# EtherIOv3_1.net
KiCad netlist of a schematic drawn in Altium Designer
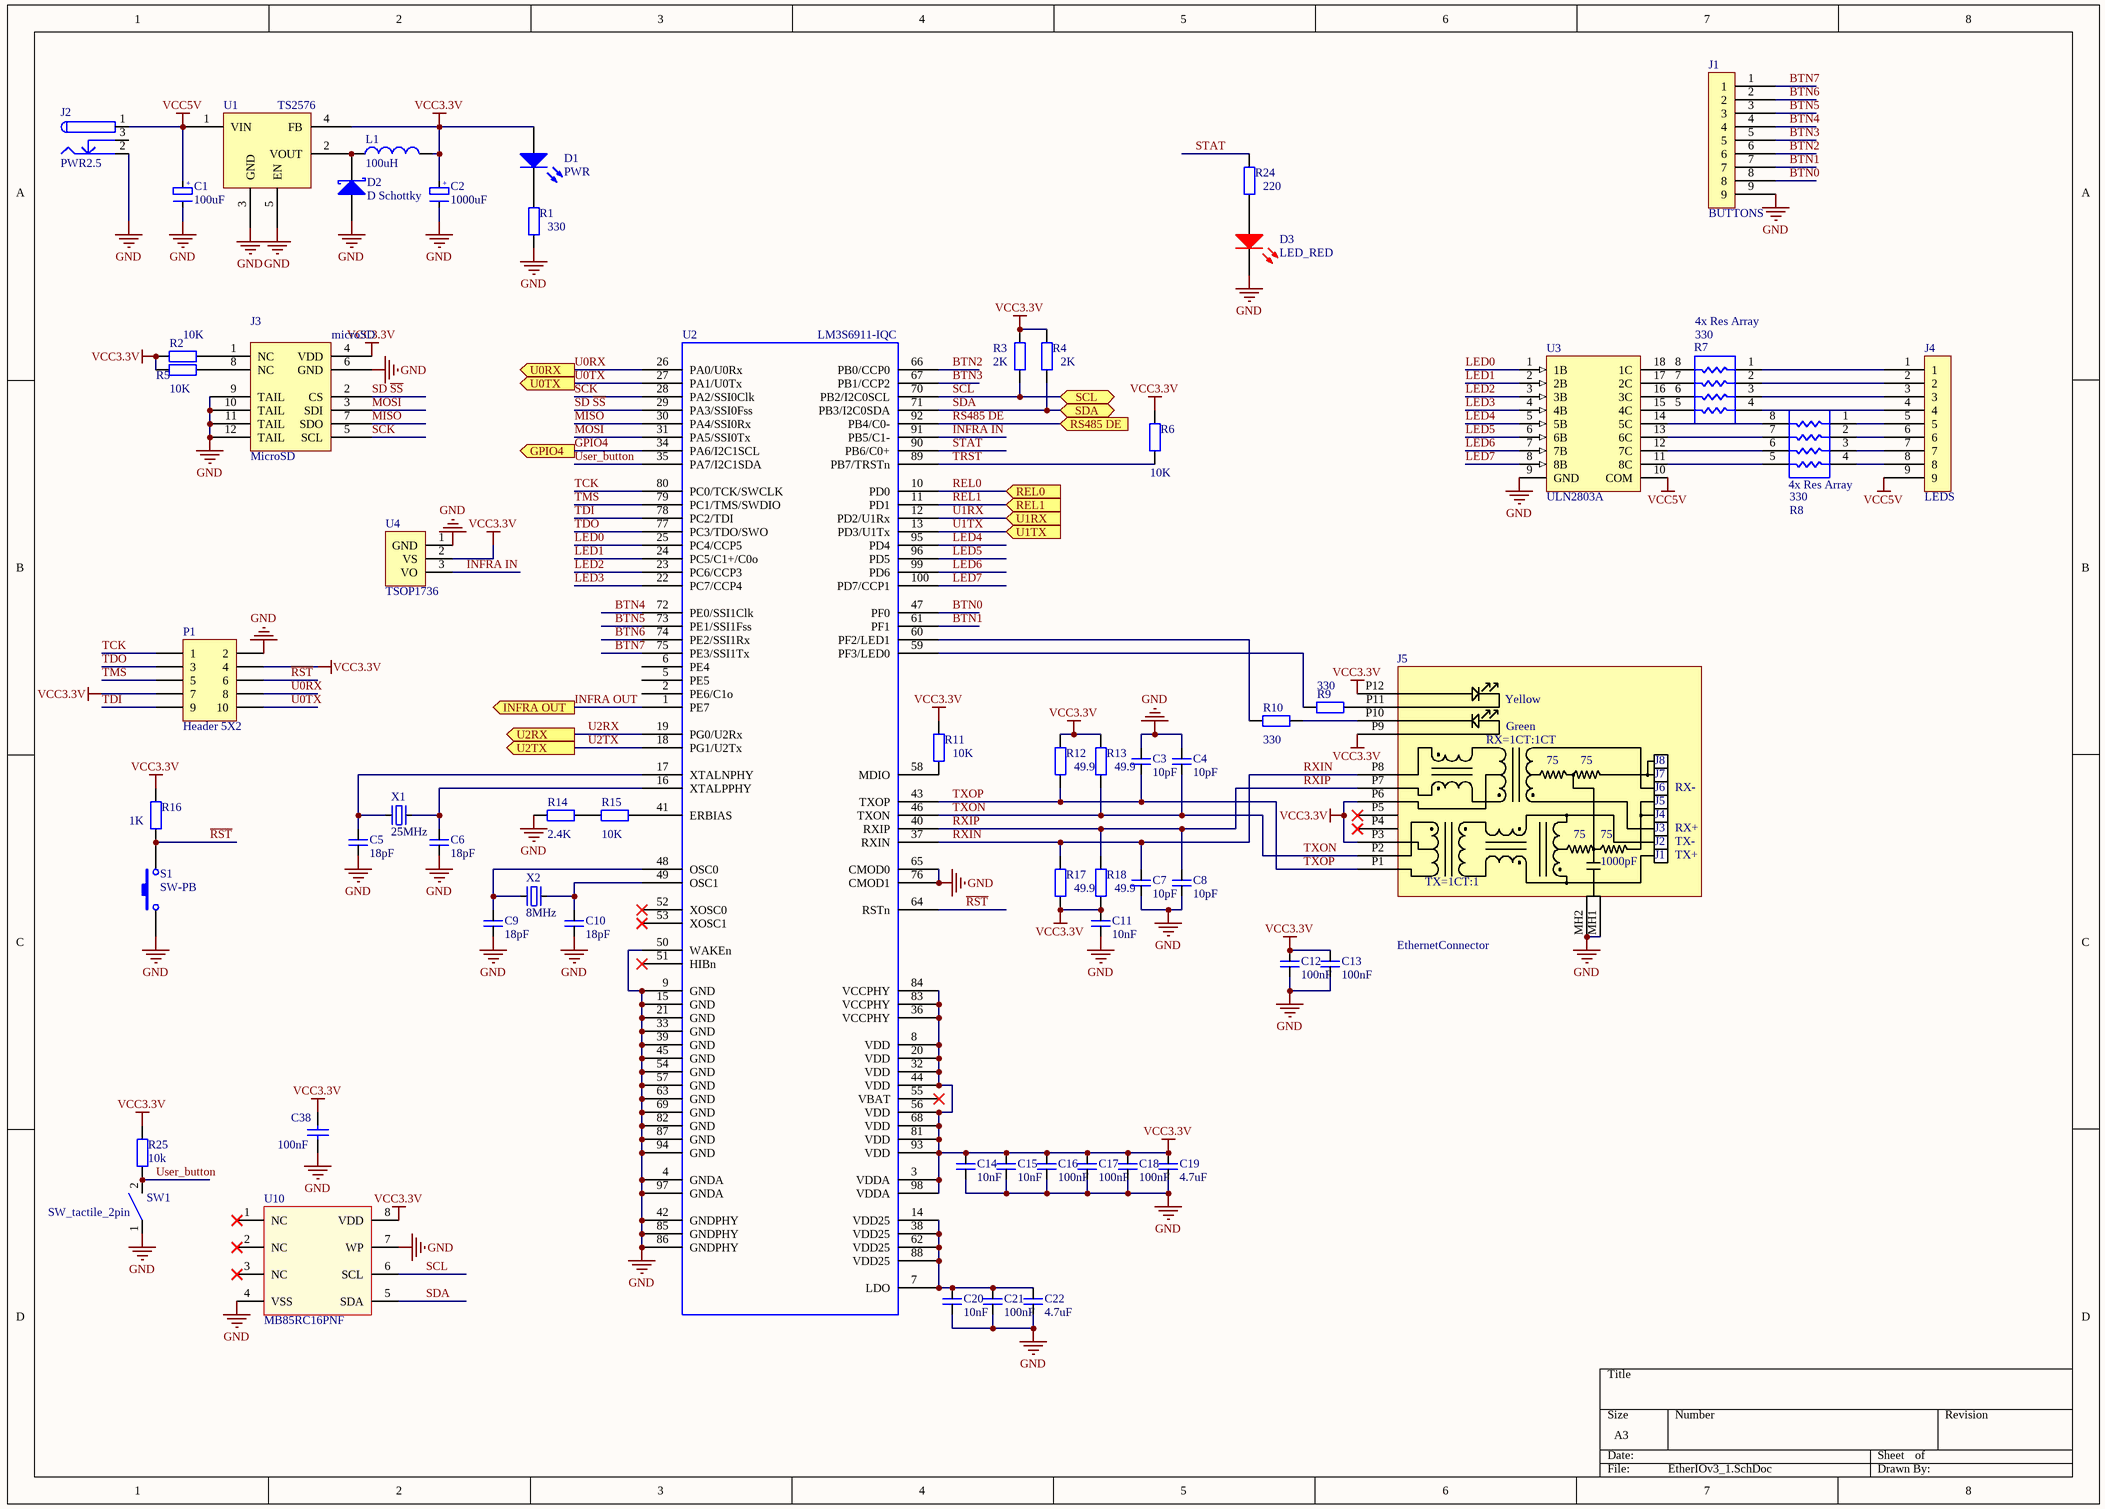
[diagram p0: EtherIOv3_1.SchDoc]

(export (version "E")
  (design (tool "Eeschema 10.0.6"))
  (components
    (comp (ref "C1")
      (value "100uF")
      (footprint "Electrolit Cap F80")
      (description "SMD Electrolit Capacitor")
      (fields (field (name "Comment") "100uF_25V"))
      (libsource (lib "EtherIOv2") (part "100uF_25V"))
    )
    (comp (ref "C2")
      (value "1000uF")
      (footprint "Electrolit Cap J10")
      (description "SMD Electrolit Capacitor")
      (fields (field (name "Comment") "1000uF_6V3"))
      (libsource (lib "EtherIOv2") (part "1000uF_6V3"))
    )
    (comp (ref "C3")
      (value "10pF")
      (footprint "0805 CAP")
      (description "Capacitor")
      (fields (field (name "Comment") "CAP"))
      (libsource (lib "EtherIOv2") (part "CAP"))
    )
    (comp (ref "C4")
      (value "10pF")
      (footprint "0805 CAP")
      (description "Capacitor")
      (fields (field (name "Comment") "CAP"))
      (libsource (lib "EtherIOv2") (part "CAP"))
    )
    (comp (ref "C5")
      (value "18pF")
      (footprint "0805 CAP")
      (description "Capacitor")
      (fields (field (name "Comment") "CAP"))
      (libsource (lib "EtherIOv2") (part "CAP"))
    )
    (comp (ref "C6")
      (value "18pF")
      (footprint "0805 CAP")
      (description "Capacitor")
      (fields (field (name "Comment") "CAP"))
      (libsource (lib "EtherIOv2") (part "CAP"))
    )
    (comp (ref "C7")
      (value "10pF")
      (footprint "0805 CAP")
      (description "Capacitor")
      (fields (field (name "Comment") "CAP"))
      (libsource (lib "EtherIOv2") (part "CAP"))
    )
    (comp (ref "C8")
      (value "10pF")
      (footprint "0805 CAP")
      (description "Capacitor")
      (fields (field (name "Comment") "CAP"))
      (libsource (lib "EtherIOv2") (part "CAP"))
    )
    (comp (ref "C9")
      (value "18pF")
      (footprint "0805 CAP")
      (description "Capacitor")
      (fields (field (name "Comment") "CAP"))
      (libsource (lib "EtherIOv2") (part "CAP"))
    )
    (comp (ref "C10")
      (value "18pF")
      (footprint "0805 CAP")
      (description "Capacitor")
      (fields (field (name "Comment") "CAP"))
      (libsource (lib "EtherIOv2") (part "CAP"))
    )
    (comp (ref "C11")
      (value "10nF")
      (footprint "0805 CAP")
      (description "Capacitor")
      (fields (field (name "Comment") "CAP"))
      (libsource (lib "EtherIOv2") (part "CAP"))
    )
    (comp (ref "C12")
      (value "100nF")
      (footprint "0805 CAP")
      (description "Capacitor")
      (fields (field (name "Comment") "CAP"))
      (libsource (lib "EtherIOv2") (part "CAP"))
    )
    (comp (ref "C13")
      (value "100nF")
      (footprint "0805 CAP")
      (description "Capacitor")
      (fields (field (name "Comment") "CAP"))
      (libsource (lib "EtherIOv2") (part "CAP"))
    )
    (comp (ref "C14")
      (value "10nF")
      (footprint "0805 CAP")
      (description "Capacitor")
      (fields (field (name "Comment") "CAP"))
      (libsource (lib "EtherIOv2") (part "CAP"))
    )
    (comp (ref "C15")
      (value "10nF")
      (footprint "0805 CAP")
      (description "Capacitor")
      (fields (field (name "Comment") "CAP"))
      (libsource (lib "EtherIOv2") (part "CAP"))
    )
    (comp (ref "C16")
      (value "100nF")
      (footprint "0805 CAP")
      (description "Capacitor")
      (fields (field (name "Comment") "CAP"))
      (libsource (lib "EtherIOv2") (part "CAP"))
    )
    (comp (ref "C17")
      (value "100nF")
      (footprint "0805 CAP")
      (description "Capacitor")
      (fields (field (name "Comment") "CAP"))
      (libsource (lib "EtherIOv2") (part "CAP"))
    )
    (comp (ref "C18")
      (value "100nF")
      (footprint "0805 CAP")
      (description "Capacitor")
      (fields (field (name "Comment") "CAP"))
      (libsource (lib "EtherIOv2") (part "CAP"))
    )
    (comp (ref "C19")
      (value "4.7uF")
      (footprint "0805 CAP")
      (description "Capacitor")
      (fields (field (name "Comment") "CAP"))
      (libsource (lib "EtherIOv2") (part "CAP"))
    )
    (comp (ref "C20")
      (value "10nF")
      (footprint "0805 CAP")
      (description "Capacitor")
      (fields (field (name "Comment") "CAP"))
      (libsource (lib "EtherIOv2") (part "CAP"))
    )
    (comp (ref "C21")
      (value "100nF")
      (footprint "0805 CAP")
      (description "Capacitor")
      (fields (field (name "Comment") "CAP"))
      (libsource (lib "EtherIOv2") (part "CAP"))
    )
    (comp (ref "C22")
      (value "4.7uF")
      (footprint "0805 CAP")
      (description "Capacitor")
      (fields (field (name "Comment") "CAP"))
      (libsource (lib "EtherIOv2") (part "CAP"))
    )
    (comp (ref "C38")
      (value "100nF")
      (footprint "FP_0805_CAP_125")
      (description "Capacitor")
      (libsource (lib "Miscellaneous Devices") (part "Cap"))
    )
    (comp (ref "D1")
      (value "PWR")
      (footprint "0805 LED")
      (description "Typical RED, GREEN, YELLOW, AMBER GaAs LED")
      (fields (field (name "PUBLISHER") "Altium Limited"))
      (libsource (lib "Miscellaneous Devices") (part "LED2"))
    )
    (comp (ref "D2")
      (value "D Schottky")
      (footprint "DSO-C2/X2.3")
      (description "Schottky Diode")
      (fields (field (name "PUBLISHER") "Altium Limited"))
      (libsource (lib "Miscellaneous Devices") (part "D Schottky"))
    )
    (comp (ref "D3")
      (value "LED_RED")
      (footprint "Osram sideled")
      (description "Typical LED")
      (libsource (lib "Led_optical") (part "LED_R"))
    )
    (comp (ref "J1")
      (value "BUTTONS")
      (footprint "Euroblock 3.5pitch 9P")
      (libsource (lib "") (part "Euroblock 9P connector_1"))
    )
    (comp (ref "J2")
      (value "PWR2.5")
      (footprint "KLD-0202")
      (description "Low Voltage Power Supply Connector")
      (fields (field (name "PUBLISHER") "Altium Limited"))
      (libsource (lib "EtherIOv2") (part "PWR2.5"))
    )
    (comp (ref "J3") (value "MicroSD") (footprint "microSD") (libsource (lib "Waterstars") (part "MicroSD")))
    (comp (ref "J4")
      (value "LEDS")
      (footprint "Euroblock 3.5pitch 9P")
      (libsource (lib "EtherIOv2") (part "Euroblock 9P connector"))
    )
    (comp (ref "J5")
      (value "EthernetConnector")
      (footprint "LU1T516-43")
      (libsource (lib "EtherIOv2") (part "EthernetConnector"))
    )
    (comp (ref "L1")
      (value "100uH")
      (footprint "INDP127127X85N")
      (description "Inductor")
      (fields (field (name "PUBLISHER") "Altium Limited"))
      (libsource (lib "Miscellaneous Devices") (part "Inductor"))
    )
    (comp (ref "P1")
      (value "Header 5X2")
      (footprint "IDC2.54-V10D")
      (description "Header, 5-Pin, Dual row")
      (fields (field (name "PUBLISHER") "Altium Limited"))
      (libsource (lib "EtherIOv2") (part "Header 5X2"))
    )
    (comp (ref "R1")
      (value "330")
      (footprint "0805 RES")
      (description "Resistor")
      (fields (field (name "Comment") "RES") (field (name "PUBLISHER") "Altium Limited"))
      (libsource (lib "") (part "RES_1"))
    )
    (comp (ref "R2")
      (value "10K")
      (footprint "0805 RES")
      (description "Resistor")
      (fields (field (name "Comment") "RES") (field (name "PUBLISHER") "Altium Limited"))
      (libsource (lib "") (part "RES_2"))
    )
    (comp (ref "R3")
      (value "2K")
      (footprint "0805 RES")
      (description "Resistor")
      (fields (field (name "Comment") "RES") (field (name "PUBLISHER") "Altium Limited"))
      (libsource (lib "") (part "RES_1"))
    )
    (comp (ref "R4")
      (value "2K")
      (footprint "0805 RES")
      (description "Resistor")
      (fields (field (name "Comment") "RES") (field (name "PUBLISHER") "Altium Limited"))
      (libsource (lib "") (part "RES_1"))
    )
    (comp (ref "R5")
      (value "10K")
      (footprint "0805 RES")
      (description "Resistor")
      (fields (field (name "Comment") "RES") (field (name "PUBLISHER") "Altium Limited"))
      (libsource (lib "") (part "RES_2"))
    )
    (comp (ref "R6")
      (value "10K")
      (footprint "0805 RES")
      (description "Resistor")
      (fields (field (name "Comment") "RES") (field (name "PUBLISHER") "Altium Limited"))
      (libsource (lib "") (part "RES_1"))
    )
    (comp (ref "R7")
      (value "4x Res Array")
      (footprint "1206 4xRES ARRAY")
      (description "Isolated Resistor Network")
      (fields (field (name "ALTIUM_VALUE") "330") (field (name "PUBLISHER") "Altium Limited"))
      (libsource (lib "EtherIOv2") (part "4x Res Array"))
    )
    (comp (ref "R8")
      (value "4x Res Array")
      (footprint "1206 4xRES ARRAY")
      (description "Isolated Resistor Network")
      (fields (field (name "ALTIUM_VALUE") "330") (field (name "PUBLISHER") "Altium Limited"))
      (libsource (lib "EtherIOv2") (part "4x Res Array"))
    )
    (comp (ref "R9")
      (value "330")
      (footprint "0805 RES")
      (description "Resistor")
      (fields (field (name "Comment") "RES") (field (name "PUBLISHER") "Altium Limited"))
      (libsource (lib "") (part "RES_3"))
    )
    (comp (ref "R10")
      (value "330")
      (footprint "0805 RES")
      (description "Resistor")
      (fields (field (name "Comment") "RES") (field (name "PUBLISHER") "Altium Limited"))
      (libsource (lib "") (part "RES_3"))
    )
    (comp (ref "R11")
      (value "10K")
      (footprint "0805 RES")
      (description "Resistor")
      (fields (field (name "Comment") "RES") (field (name "PUBLISHER") "Altium Limited"))
      (libsource (lib "") (part "RES_1"))
    )
    (comp (ref "R12")
      (value "49.9")
      (footprint "0805 RES")
      (description "Resistor")
      (fields (field (name "Comment") "RES") (field (name "PUBLISHER") "Altium Limited"))
      (libsource (lib "") (part "RES_1"))
    )
    (comp (ref "R13")
      (value "49.9")
      (footprint "0805 RES")
      (description "Resistor")
      (fields (field (name "Comment") "RES") (field (name "PUBLISHER") "Altium Limited"))
      (libsource (lib "") (part "RES_1"))
    )
    (comp (ref "R14")
      (value "2.4K")
      (footprint "0805 RES")
      (description "Resistor")
      (fields (field (name "Comment") "RES") (field (name "PUBLISHER") "Altium Limited"))
      (libsource (lib "") (part "RES_3"))
    )
    (comp (ref "R15")
      (value "10K")
      (footprint "0805 RES")
      (description "Resistor")
      (fields (field (name "Comment") "RES") (field (name "PUBLISHER") "Altium Limited"))
      (libsource (lib "") (part "RES_3"))
    )
    (comp (ref "R16")
      (value "1K")
      (footprint "0805 RES")
      (description "Resistor")
      (fields (field (name "Comment") "RES") (field (name "PUBLISHER") "Altium Limited"))
      (libsource (lib "") (part "RES_1"))
    )
    (comp (ref "R17")
      (value "49.9")
      (footprint "0805 RES")
      (description "Resistor")
      (fields (field (name "Comment") "RES") (field (name "PUBLISHER") "Altium Limited"))
      (libsource (lib "EtherIOv2") (part "RES"))
    )
    (comp (ref "R18")
      (value "49.9")
      (footprint "0805 RES")
      (description "Resistor")
      (fields (field (name "Comment") "RES") (field (name "PUBLISHER") "Altium Limited"))
      (libsource (lib "EtherIOv2") (part "RES"))
    )
    (comp (ref "R24")
      (value "220")
      (footprint "0805 RES")
      (description "Resistor")
      (fields (field (name "Comment") "RES") (field (name "PUBLISHER") "Altium Limited"))
      (libsource (lib "") (part "RES_1"))
    )
    (comp (ref "R25")
      (value "10k")
      (footprint "FP_0805_RES")
      (description "Resistor")
      (libsource (lib "Miscellaneous Devices") (part "Res3"))
    )
    (comp (ref "S1")
      (value "SW-PB")
      (footprint "SPST-2")
      (description "Switch")
      (fields (field (name "PUBLISHER") "Altium Limited"))
      (libsource (lib "EtherIOv2") (part "SW-PB"))
    )
    (comp (ref "SW1")
      (value "SW_tactile_2pin")
      (footprint "BUTTON_6X6 90deg")
      (libsource (lib "Switch") (part "SW_tactile_2pin"))
    )
    (comp (ref "U1")
      (value "TS2576")
      (footprint "TO-263-5L")
      (description "Step Down DC-DC Converter")
      (libsource (lib "EtherIOv2") (part "TS2576"))
    )
    (comp (ref "U2")
      (value "LM3S6911-IQC")
      (footprint "Luminary+Micro:QFP50P1600X1600X160-100N")
      (description "Stellaris ARM Cortex-M3 Microcontroller")
      (fields (field (name "MFG") "Luminary Micro"))
      (libsource (lib "Luminary+Micro") (part "LM3S6611-IQC"))
    )
    (comp (ref "U3")
      (value "ULN2803A")
      (footprint "SOIC127P1030X265-18N")
      (description "8xDarlington Driver")
      (libsource (lib "EtherIOv2") (part "ULN2803A"))
    )
    (comp (ref "U4")
      (value "TSOP1736")
      (footprint "TSOP17xx")
      (description "IR Receiver, 3-Pin")
      (fields (field (name "PUBLISHER") "Altium Limited"))
      (libsource (lib "EtherIOv2") (part "TSOP17xx"))
    )
    (comp (ref "U10")
      (value "MB85RC16PNF")
      (footprint "DIGITAL_SOIC8")
      (description "MB85RC16PNF I2C MEM")
      (libsource (lib "Digital") (part "MB85RC16PNF"))
    )
    (comp (ref "X1")
      (value "25MHz")
      (footprint "CRYSTAL_LOW")
      (description "Crystal")
      (fields (field (name "Comment") "CRYSTAL"))
      (libsource (lib "EtherIOv2") (part "CRYSTAL"))
    )
    (comp (ref "X2")
      (value "8MHz")
      (footprint "CRYSTAL_LOW")
      (description "Crystal")
      (fields (field (name "Comment") "CRYSTAL"))
      (libsource (lib "EtherIOv2") (part "CRYSTAL"))
    )
  )
  (nets
    (net (code "1") (name "/BTN0") (class "Default")
      (node (ref "J1") (pin "8") (pinfunction "8_8") (pintype "passive"))
      (node (ref "U2") (pin "47") (pinfunction "PF0_47") (pintype "passive"))
    )
    (net (code "2") (name "/BTN1") (class "Default")
      (node (ref "J1") (pin "7") (pinfunction "7_7") (pintype "passive"))
      (node (ref "U2") (pin "61") (pinfunction "PF1_61") (pintype "passive"))
    )
    (net (code "3") (name "/BTN2") (class "Default")
      (node (ref "J1") (pin "6") (pinfunction "6_6") (pintype "passive"))
      (node (ref "U2") (pin "66") (pinfunction "PB0/CCP0_66") (pintype "passive"))
    )
    (net (code "4") (name "/BTN3") (class "Default")
      (node (ref "J1") (pin "5") (pinfunction "5_5") (pintype "passive"))
      (node (ref "U2") (pin "67") (pinfunction "PB1/CCP2_67") (pintype "passive"))
    )
    (net (code "5") (name "/BTN4") (class "Default")
      (node (ref "J1") (pin "4") (pinfunction "4_4") (pintype "passive"))
      (node (ref "U2") (pin "72") (pinfunction "PE0/SSI1Clk_72") (pintype "passive"))
    )
    (net (code "6") (name "/BTN5") (class "Default")
      (node (ref "J1") (pin "3") (pinfunction "3_3") (pintype "passive"))
      (node (ref "U2") (pin "73") (pinfunction "PE1/SSI1Fss_73") (pintype "passive"))
    )
    (net (code "7") (name "/BTN6") (class "Default")
      (node (ref "J1") (pin "2") (pinfunction "2_2") (pintype "passive"))
      (node (ref "U2") (pin "74") (pinfunction "PE2/SSI1Rx_74") (pintype "passive"))
    )
    (net (code "8") (name "/BTN7") (class "Default")
      (node (ref "J1") (pin "1") (pinfunction "1_1") (pintype "passive"))
      (node (ref "U2") (pin "75") (pinfunction "PE3/SSI1Tx_75") (pintype "passive"))
    )
    (net (code "9") (name "/GPIO4") (class "Default")
      (node (ref "U2") (pin "34") (pinfunction "PA6/I2C1SCL_34") (pintype "passive"))
    )
    (net (code "10") (name "/INFRA IN") (class "Default")
      (node (ref "U2") (pin "91") (pinfunction "PB5/C1-_91") (pintype "passive"))
      (node (ref "U4") (pin "3") (pinfunction "VO_3") (pintype "passive"))
    )
    (net (code "11") (name "/INFRA OUT") (class "Default")
      (node (ref "U2") (pin "1") (pinfunction "PE7_1") (pintype "passive"))
    )
    (net (code "12") (name "/LED0") (class "Default")
      (node (ref "U2") (pin "25") (pinfunction "PC4/CCP5_25") (pintype "passive"))
      (node (ref "U3") (pin "1") (pinfunction "1B_1") (pintype "input"))
    )
    (net (code "13") (name "/LED1") (class "Default")
      (node (ref "U2") (pin "24") (pinfunction "PC5/C1+/C0o_24") (pintype "passive"))
      (node (ref "U3") (pin "2") (pinfunction "2B_2") (pintype "input"))
    )
    (net (code "14") (name "/LED2") (class "Default")
      (node (ref "U2") (pin "23") (pinfunction "PC6/CCP3_23") (pintype "passive"))
      (node (ref "U3") (pin "3") (pinfunction "3B_3") (pintype "input"))
    )
    (net (code "15") (name "/LED3") (class "Default")
      (node (ref "U2") (pin "22") (pinfunction "PC7/CCP4_22") (pintype "passive"))
      (node (ref "U3") (pin "4") (pinfunction "4B_4") (pintype "input"))
    )
    (net (code "16") (name "/LED4") (class "Default")
      (node (ref "U2") (pin "95") (pinfunction "PD4_95") (pintype "passive"))
      (node (ref "U3") (pin "5") (pinfunction "5B_5") (pintype "input"))
    )
    (net (code "17") (name "/LED5") (class "Default")
      (node (ref "U2") (pin "96") (pinfunction "PD5_96") (pintype "passive"))
      (node (ref "U3") (pin "6") (pinfunction "6B_6") (pintype "input"))
    )
    (net (code "18") (name "/LED6") (class "Default")
      (node (ref "U2") (pin "99") (pinfunction "PD6_99") (pintype "passive"))
      (node (ref "U3") (pin "7") (pinfunction "7B_7") (pintype "input"))
    )
    (net (code "19") (name "/LED7") (class "Default")
      (node (ref "U2") (pin "100") (pinfunction "PD7/CCP1_100") (pintype "passive"))
      (node (ref "U3") (pin "8") (pinfunction "8B_8") (pintype "input"))
    )
    (net (code "20") (name "/MISO") (class "Default")
      (node (ref "J3") (pin "7") (pinfunction "SDO_7") (pintype "passive"))
      (node (ref "U2") (pin "30") (pinfunction "PA4/SSI0Rx_30") (pintype "passive"))
    )
    (net (code "21") (name "/MOSI") (class "Default")
      (node (ref "J3") (pin "3") (pinfunction "SDI_3") (pintype "passive"))
      (node (ref "U2") (pin "31") (pinfunction "PA5/SSI0Tx_31") (pintype "passive"))
    )
    (net (code "22") (name "/REL0") (class "Default")
      (node (ref "U2") (pin "10") (pinfunction "PD0_10") (pintype "passive"))
    )
    (net (code "23") (name "/REL1") (class "Default")
      (node (ref "U2") (pin "11") (pinfunction "PD1_11") (pintype "passive"))
    )
    (net (code "24") (name "/RS485 DE") (class "Default")
      (node (ref "U2") (pin "92") (pinfunction "PB4/C0-_92") (pintype "passive"))
    )
    (net (code "25") (name "/RXIN") (class "Default")
      (node (ref "C7") (pin "1") (pinfunction "A_1") (pintype "passive"))
      (node (ref "J5") (pin "P8") (pinfunction "P8_P8") (pintype "passive"))
      (node (ref "R17") (pin "1") (pinfunction "1_1") (pintype "passive"))
      (node (ref "U2") (pin "37") (pinfunction "RXIN_37") (pintype "passive"))
    )
    (net (code "26") (name "/RXIP") (class "Default")
      (node (ref "C8") (pin "1") (pinfunction "A_1") (pintype "passive"))
      (node (ref "J5") (pin "P7") (pinfunction "P7_P7") (pintype "passive"))
      (node (ref "R18") (pin "1") (pinfunction "1_1") (pintype "passive"))
      (node (ref "U2") (pin "40") (pinfunction "RXIP_40") (pintype "passive"))
    )
    (net (code "27") (name "/SCK") (class "Default")
      (node (ref "J3") (pin "5") (pinfunction "SCL_5") (pintype "passive"))
      (node (ref "U2") (pin "28") (pinfunction "PA2/SSI0Clk_28") (pintype "passive"))
    )
    (net (code "28") (name "/SCL") (class "Default")
      (node (ref "R3") (pin "1") (pinfunction "1_1") (pintype "passive"))
      (node (ref "U10") (pin "6") (pinfunction "SCL_6") (pintype "passive"))
      (node (ref "U2") (pin "70") (pinfunction "PB2/I2C0SCL_70") (pintype "passive"))
    )
    (net (code "29") (name "/SD ~{SS}") (class "Default")
      (node (ref "J3") (pin "2") (pinfunction "CS_2") (pintype "passive"))
      (node (ref "U2") (pin "29") (pinfunction "PA3/SSI0Fss_29") (pintype "passive"))
    )
    (net (code "30") (name "/SDA") (class "Default")
      (node (ref "R4") (pin "1") (pinfunction "1_1") (pintype "passive"))
      (node (ref "U10") (pin "5") (pinfunction "SDA_5") (pintype "passive"))
      (node (ref "U2") (pin "71") (pinfunction "PB3/I2C0SDA_71") (pintype "passive"))
    )
    (net (code "31") (name "/STAT") (class "Default")
      (node (ref "R24") (pin "2") (pinfunction "2_2") (pintype "passive"))
      (node (ref "U2") (pin "90") (pinfunction "PB6/C0+_90") (pintype "passive"))
    )
    (net (code "32") (name "/TCK") (class "Default")
      (node (ref "P1") (pin "1") (pinfunction "1_1") (pintype "passive"))
      (node (ref "U2") (pin "80") (pinfunction "PC0/TCK/SWCLK_80") (pintype "passive"))
    )
    (net (code "33") (name "/TDI") (class "Default")
      (node (ref "P1") (pin "9") (pinfunction "9_9") (pintype "passive"))
      (node (ref "U2") (pin "78") (pinfunction "PC2/TDI_78") (pintype "passive"))
    )
    (net (code "34") (name "/TDO") (class "Default")
      (node (ref "P1") (pin "3") (pinfunction "3_3") (pintype "passive"))
      (node (ref "U2") (pin "77") (pinfunction "PC3/TDO/SWO_77") (pintype "passive"))
    )
    (net (code "35") (name "/TMS") (class "Default")
      (node (ref "P1") (pin "5") (pinfunction "5_5") (pintype "passive"))
      (node (ref "U2") (pin "79") (pinfunction "PC1/TMS/SWDIO_79") (pintype "passive"))
    )
    (net (code "36") (name "/TXON") (class "Default")
      (node (ref "C4") (pin "1") (pinfunction "A_1") (pintype "passive"))
      (node (ref "J5") (pin "P2") (pinfunction "P2_P2") (pintype "passive"))
      (node (ref "R13") (pin "1") (pinfunction "1_1") (pintype "passive"))
      (node (ref "U2") (pin "46") (pinfunction "TXON_46") (pintype "passive"))
    )
    (net (code "37") (name "/TXOP") (class "Default")
      (node (ref "C3") (pin "1") (pinfunction "A_1") (pintype "passive"))
      (node (ref "J5") (pin "P1") (pinfunction "P1_P1") (pintype "passive"))
      (node (ref "R12") (pin "1") (pinfunction "1_1") (pintype "passive"))
      (node (ref "U2") (pin "43") (pinfunction "TXOP_43") (pintype "passive"))
    )
    (net (code "38") (name "/U0RX") (class "Default")
      (node (ref "P1") (pin "8") (pinfunction "8_8") (pintype "passive"))
      (node (ref "U2") (pin "26") (pinfunction "PA0/U0Rx_26") (pintype "passive"))
    )
    (net (code "39") (name "/U0TX") (class "Default")
      (node (ref "P1") (pin "10") (pinfunction "10_10") (pintype "passive"))
      (node (ref "U2") (pin "27") (pinfunction "PA1/U0Tx_27") (pintype "passive"))
    )
    (net (code "40") (name "/U1RX") (class "Default")
      (node (ref "U2") (pin "12") (pinfunction "PD2/U1Rx_12") (pintype "passive"))
    )
    (net (code "41") (name "/U1TX") (class "Default")
      (node (ref "U2") (pin "13") (pinfunction "PD3/U1Tx_13") (pintype "passive"))
    )
    (net (code "42") (name "/U2RX") (class "Default")
      (node (ref "U2") (pin "19") (pinfunction "PG0/U2Rx_19") (pintype "passive"))
    )
    (net (code "43") (name "/U2TX") (class "Default")
      (node (ref "U2") (pin "18") (pinfunction "PG1/U2Tx_18") (pintype "passive"))
    )
    (net (code "44") (name "/User_button") (class "Default")
      (node (ref "R25") (pin "2") (pinfunction "2_2") (pintype "passive"))
      (node (ref "SW1") (pin "2") (pinfunction "2_2") (pintype "passive"))
      (node (ref "U2") (pin "35") (pinfunction "PA7/I2C1SDA_35") (pintype "passive"))
    )
    (net (code "45") (name "/~{RST}") (class "Default")
      (node (ref "P1") (pin "6") (pinfunction "6_6") (pintype "passive"))
      (node (ref "R16") (pin "1") (pinfunction "1_1") (pintype "passive"))
      (node (ref "S1") (pin "2") (pinfunction "2_2") (pintype "passive"))
      (node (ref "U2") (pin "64") (pinfunction "RSTn_64") (pintype "passive"))
    )
    (net (code "46") (name "/~{TRST}") (class "Default")
      (node (ref "R6") (pin "1") (pinfunction "1_1") (pintype "passive"))
      (node (ref "U2") (pin "89") (pinfunction "PB7/TRSTn_89") (pintype "passive"))
    )
    (net (code "47") (name "GND") (class "Default")
      (node (ref "C1") (pin "1") (pinfunction "B_1") (pintype "passive"))
      (node (ref "C10") (pin "1") (pinfunction "A_1") (pintype "passive"))
      (node (ref "C11") (pin "1") (pinfunction "A_1") (pintype "passive"))
      (node (ref "C12") (pin "2") (pinfunction "B_2") (pintype "passive"))
      (node (ref "C13") (pin "2") (pinfunction "B_2") (pintype "passive"))
      (node (ref "C14") (pin "1") (pinfunction "A_1") (pintype "passive"))
      (node (ref "C15") (pin "1") (pinfunction "A_1") (pintype "passive"))
      (node (ref "C16") (pin "1") (pinfunction "A_1") (pintype "passive"))
      (node (ref "C17") (pin "1") (pinfunction "A_1") (pintype "passive"))
      (node (ref "C18") (pin "1") (pinfunction "A_1") (pintype "passive"))
      (node (ref "C19") (pin "1") (pinfunction "A_1") (pintype "passive"))
      (node (ref "C2") (pin "1") (pinfunction "B_1") (pintype "passive"))
      (node (ref "C20") (pin "1") (pinfunction "A_1") (pintype "passive"))
      (node (ref "C21") (pin "1") (pinfunction "A_1") (pintype "passive"))
      (node (ref "C22") (pin "1") (pinfunction "A_1") (pintype "passive"))
      (node (ref "C3") (pin "2") (pinfunction "B_2") (pintype "passive"))
      (node (ref "C38") (pin "2") (pinfunction "2_2") (pintype "passive"))
      (node (ref "C4") (pin "2") (pinfunction "B_2") (pintype "passive"))
      (node (ref "C5") (pin "1") (pinfunction "A_1") (pintype "passive"))
      (node (ref "C6") (pin "1") (pinfunction "A_1") (pintype "passive"))
      (node (ref "C7") (pin "2") (pinfunction "B_2") (pintype "passive"))
      (node (ref "C8") (pin "2") (pinfunction "B_2") (pintype "passive"))
      (node (ref "C9") (pin "1") (pinfunction "A_1") (pintype "passive"))
      (node (ref "D2") (pin "1") (pinfunction "A_1") (pintype "passive"))
      (node (ref "D3") (pin "K") (pinfunction "K_K") (pintype "passive"))
      (node (ref "J1") (pin "9") (pinfunction "9_9") (pintype "passive"))
      (node (ref "J2") (pin "2") (pinfunction "2_2") (pintype "passive"))
      (node (ref "J3") (pin "10") (pinfunction "TAIL_10") (pintype "passive"))
      (node (ref "J3") (pin "11") (pinfunction "TAIL_11") (pintype "passive"))
      (node (ref "J3") (pin "12") (pinfunction "TAIL_12") (pintype "passive"))
      (node (ref "J3") (pin "6") (pinfunction "GND_6") (pintype "passive"))
      (node (ref "J3") (pin "9") (pinfunction "TAIL_9") (pintype "passive"))
      (node (ref "J5") (pin "MH1") (pinfunction "SHIELD_MH1") (pintype "passive"))
      (node (ref "J5") (pin "MH2") (pinfunction "SHIELD_MH2") (pintype "passive"))
      (node (ref "P1") (pin "2") (pinfunction "2_2") (pintype "passive"))
      (node (ref "R1") (pin "1") (pinfunction "1_1") (pintype "passive"))
      (node (ref "R14") (pin "1") (pinfunction "1_1") (pintype "passive"))
      (node (ref "S1") (pin "1") (pinfunction "1_1") (pintype "passive"))
      (node (ref "SW1") (pin "1") (pinfunction "1_1") (pintype "passive"))
      (node (ref "U1") (pin "3") (pinfunction "GND_3") (pintype "power_in"))
      (node (ref "U1") (pin "5") (pinfunction "EN_5") (pintype "passive"))
      (node (ref "U10") (pin "4") (pinfunction "VSS_4") (pintype "passive"))
      (node (ref "U10") (pin "7") (pinfunction "WP_7") (pintype "passive"))
      (node (ref "U2") (pin "15") (pinfunction "GND_15") (pintype "passive"))
      (node (ref "U2") (pin "21") (pinfunction "GND_21") (pintype "passive"))
      (node (ref "U2") (pin "33") (pinfunction "GND_33") (pintype "passive"))
      (node (ref "U2") (pin "39") (pinfunction "GND_39") (pintype "passive"))
      (node (ref "U2") (pin "4") (pinfunction "GNDA_4") (pintype "passive"))
      (node (ref "U2") (pin "42") (pinfunction "GNDPHY_42") (pintype "passive"))
      (node (ref "U2") (pin "45") (pinfunction "GND_45") (pintype "passive"))
      (node (ref "U2") (pin "50") (pinfunction "WAKEn_50") (pintype "passive"))
      (node (ref "U2") (pin "54") (pinfunction "GND_54") (pintype "passive"))
      (node (ref "U2") (pin "57") (pinfunction "GND_57") (pintype "passive"))
      (node (ref "U2") (pin "63") (pinfunction "GND_63") (pintype "passive"))
      (node (ref "U2") (pin "65") (pinfunction "CMOD0_65") (pintype "passive"))
      (node (ref "U2") (pin "69") (pinfunction "GND_69") (pintype "passive"))
      (node (ref "U2") (pin "76") (pinfunction "CMOD1_76") (pintype "passive"))
      (node (ref "U2") (pin "82") (pinfunction "GND_82") (pintype "passive"))
      (node (ref "U2") (pin "85") (pinfunction "GNDPHY_85") (pintype "passive"))
      (node (ref "U2") (pin "86") (pinfunction "GNDPHY_86") (pintype "passive"))
      (node (ref "U2") (pin "87") (pinfunction "GND_87") (pintype "passive"))
      (node (ref "U2") (pin "9") (pinfunction "GND_9") (pintype "passive"))
      (node (ref "U2") (pin "94") (pinfunction "GND_94") (pintype "passive"))
      (node (ref "U2") (pin "97") (pinfunction "GNDA_97") (pintype "passive"))
      (node (ref "U3") (pin "9") (pinfunction "GND_9") (pintype "power_in"))
      (node (ref "U4") (pin "1") (pinfunction "GND_1") (pintype "passive"))
    )
    (net (code "48") (name "Net-(C5-B)") (class "Default")
      (node (ref "C5") (pin "2") (pinfunction "B_2") (pintype "passive"))
      (node (ref "U2") (pin "17") (pinfunction "XTALNPHY_17") (pintype "passive"))
      (node (ref "X1") (pin "1") (pinfunction "A_1") (pintype "passive"))
    )
    (net (code "49") (name "Net-(C6-B)") (class "Default")
      (node (ref "C6") (pin "2") (pinfunction "B_2") (pintype "passive"))
      (node (ref "U2") (pin "16") (pinfunction "XTALPPHY_16") (pintype "passive"))
      (node (ref "X1") (pin "2") (pinfunction "B_2") (pintype "passive"))
    )
    (net (code "50") (name "Net-(C9-B)") (class "Default")
      (node (ref "C9") (pin "2") (pinfunction "B_2") (pintype "passive"))
      (node (ref "U2") (pin "48") (pinfunction "OSC0_48") (pintype "passive"))
      (node (ref "X2") (pin "1") (pinfunction "A_1") (pintype "passive"))
    )
    (net (code "51") (name "Net-(C10-B)") (class "Default")
      (node (ref "C10") (pin "2") (pinfunction "B_2") (pintype "passive"))
      (node (ref "U2") (pin "49") (pinfunction "OSC1_49") (pintype "passive"))
      (node (ref "X2") (pin "2") (pinfunction "B_2") (pintype "passive"))
    )
    (net (code "52") (name "Net-(C20-B)") (class "Default")
      (node (ref "C20") (pin "2") (pinfunction "B_2") (pintype "passive"))
      (node (ref "C21") (pin "2") (pinfunction "B_2") (pintype "passive"))
      (node (ref "C22") (pin "2") (pinfunction "B_2") (pintype "passive"))
      (node (ref "U2") (pin "14") (pinfunction "VDD25_14") (pintype "passive"))
      (node (ref "U2") (pin "38") (pinfunction "VDD25_38") (pintype "passive"))
      (node (ref "U2") (pin "62") (pinfunction "VDD25_62") (pintype "passive"))
      (node (ref "U2") (pin "7") (pinfunction "LDO_7") (pintype "passive"))
      (node (ref "U2") (pin "88") (pinfunction "VDD25_88") (pintype "passive"))
    )
    (net (code "53") (name "Net-(D1-K)") (class "Default")
      (node (ref "D1") (pin "2") (pinfunction "K_2") (pintype "passive"))
      (node (ref "R1") (pin "2") (pinfunction "2_2") (pintype "passive"))
    )
    (net (code "54") (name "Net-(D2-K)") (class "Default")
      (node (ref "D2") (pin "2") (pinfunction "K_2") (pintype "passive"))
      (node (ref "L1") (pin "1") (pinfunction "1_1") (pintype "passive"))
      (node (ref "U1") (pin "2") (pinfunction "VOUT_2") (pintype "passive"))
    )
    (net (code "55") (name "Net-(D3-PadA)") (class "Default")
      (node (ref "D3") (pin "A") (pinfunction "A_A") (pintype "passive"))
      (node (ref "R24") (pin "1") (pinfunction "1_1") (pintype "passive"))
    )
    (net (code "56") (name "Net-(J3-NC-Pad1)") (class "Default")
      (node (ref "J3") (pin "1") (pinfunction "NC_1") (pintype "passive"))
      (node (ref "R2") (pin "1") (pinfunction "1_1") (pintype "passive"))
    )
    (net (code "57") (name "Net-(J3-NC-Pad8)") (class "Default")
      (node (ref "J3") (pin "8") (pinfunction "NC_8") (pintype "passive"))
      (node (ref "R5") (pin "1") (pinfunction "1_1") (pintype "passive"))
    )
    (net (code "58") (name "Net-(J4-Pad1)") (class "Default")
      (node (ref "J4") (pin "1") (pinfunction "1_1") (pintype "passive"))
      (node (ref "R7") (pin "1") (pinfunction "1_1") (pintype "passive"))
    )
    (net (code "59") (name "Net-(J4-Pad2)") (class "Default")
      (node (ref "J4") (pin "2") (pinfunction "2_2") (pintype "passive"))
      (node (ref "R7") (pin "2") (pinfunction "2_2") (pintype "passive"))
    )
    (net (code "60") (name "Net-(J4-Pad3)") (class "Default")
      (node (ref "J4") (pin "3") (pinfunction "3_3") (pintype "passive"))
      (node (ref "R7") (pin "3") (pinfunction "3_3") (pintype "passive"))
    )
    (net (code "61") (name "Net-(J4-Pad4)") (class "Default")
      (node (ref "J4") (pin "4") (pinfunction "4_4") (pintype "passive"))
      (node (ref "R7") (pin "4") (pinfunction "4_4") (pintype "passive"))
    )
    (net (code "62") (name "Net-(J4-Pad5)") (class "Default")
      (node (ref "J4") (pin "5") (pinfunction "5_5") (pintype "passive"))
      (node (ref "R8") (pin "1") (pinfunction "1_1") (pintype "passive"))
    )
    (net (code "63") (name "Net-(J4-Pad6)") (class "Default")
      (node (ref "J4") (pin "6") (pinfunction "6_6") (pintype "passive"))
      (node (ref "R8") (pin "2") (pinfunction "2_2") (pintype "passive"))
    )
    (net (code "64") (name "Net-(J4-Pad7)") (class "Default")
      (node (ref "J4") (pin "7") (pinfunction "7_7") (pintype "passive"))
      (node (ref "R8") (pin "3") (pinfunction "3_3") (pintype "passive"))
    )
    (net (code "65") (name "Net-(J4-Pad8)") (class "Default")
      (node (ref "J4") (pin "8") (pinfunction "8_8") (pintype "passive"))
      (node (ref "R8") (pin "4") (pinfunction "4_4") (pintype "passive"))
    )
    (net (code "66") (name "Net-(J5-PadP10)") (class "Default")
      (node (ref "J5") (pin "P10") (pinfunction "P10_P10") (pintype "passive"))
      (node (ref "R10") (pin "2") (pinfunction "2_2") (pintype "passive"))
    )
    (net (code "67") (name "Net-(J5-PadP11)") (class "Default")
      (node (ref "J5") (pin "P11") (pinfunction "P11_P11") (pintype "passive"))
      (node (ref "R9") (pin "2") (pinfunction "2_2") (pintype "passive"))
    )
    (net (code "68") (name "Net-(R14-Pad2)") (class "Default")
      (node (ref "R14") (pin "2") (pinfunction "2_2") (pintype "passive"))
      (node (ref "R15") (pin "1") (pinfunction "1_1") (pintype "passive"))
    )
    (net (code "69") (name "Net-(U2-ERBIAS)") (class "Default")
      (node (ref "R15") (pin "2") (pinfunction "2_2") (pintype "passive"))
      (node (ref "U2") (pin "41") (pinfunction "ERBIAS_41") (pintype "passive"))
    )
    (net (code "70") (name "Net-(U2-MDIO)") (class "Default")
      (node (ref "R11") (pin "1") (pinfunction "1_1") (pintype "passive"))
      (node (ref "U2") (pin "58") (pinfunction "MDIO_58") (pintype "passive"))
    )
    (net (code "71") (name "Net-(U2-PF2{slash}LED1)") (class "Default")
      (node (ref "R10") (pin "1") (pinfunction "1_1") (pintype "passive"))
      (node (ref "U2") (pin "60") (pinfunction "PF2/LED1_60") (pintype "passive"))
    )
    (net (code "72") (name "Net-(U2-PF3{slash}LED0)") (class "Default")
      (node (ref "R9") (pin "1") (pinfunction "1_1") (pintype "passive"))
      (node (ref "U2") (pin "59") (pinfunction "PF3/LED0_59") (pintype "passive"))
    )
    (net (code "73") (name "Net-(U3-1C)") (class "Default")
      (node (ref "R7") (pin "8") (pinfunction "8_8") (pintype "passive"))
      (node (ref "U3") (pin "18") (pinfunction "1C_18") (pintype "open_collector"))
    )
    (net (code "74") (name "Net-(U3-2C)") (class "Default")
      (node (ref "R7") (pin "7") (pinfunction "7_7") (pintype "passive"))
      (node (ref "U3") (pin "17") (pinfunction "2C_17") (pintype "open_collector"))
    )
    (net (code "75") (name "Net-(U3-3C)") (class "Default")
      (node (ref "R7") (pin "6") (pinfunction "6_6") (pintype "passive"))
      (node (ref "U3") (pin "16") (pinfunction "3C_16") (pintype "open_collector"))
    )
    (net (code "76") (name "Net-(U3-4C)") (class "Default")
      (node (ref "R7") (pin "5") (pinfunction "5_5") (pintype "passive"))
      (node (ref "U3") (pin "15") (pinfunction "4C_15") (pintype "open_collector"))
    )
    (net (code "77") (name "Net-(U3-5C)") (class "Default")
      (node (ref "R8") (pin "8") (pinfunction "8_8") (pintype "passive"))
      (node (ref "U3") (pin "14") (pinfunction "5C_14") (pintype "open_collector"))
    )
    (net (code "78") (name "Net-(U3-6C)") (class "Default")
      (node (ref "R8") (pin "7") (pinfunction "7_7") (pintype "passive"))
      (node (ref "U3") (pin "13") (pinfunction "6C_13") (pintype "open_collector"))
    )
    (net (code "79") (name "Net-(U3-7C)") (class "Default")
      (node (ref "R8") (pin "6") (pinfunction "6_6") (pintype "passive"))
      (node (ref "U3") (pin "12") (pinfunction "7C_12") (pintype "open_collector"))
    )
    (net (code "80") (name "Net-(U3-8C)") (class "Default")
      (node (ref "R8") (pin "5") (pinfunction "5_5") (pintype "passive"))
      (node (ref "U3") (pin "11") (pinfunction "8C_11") (pintype "open_collector"))
    )
    (net (code "81") (name "VCC3.3V") (class "Default")
      (node (ref "C11") (pin "2") (pinfunction "B_2") (pintype "passive"))
      (node (ref "C12") (pin "1") (pinfunction "A_1") (pintype "passive"))
      (node (ref "C13") (pin "1") (pinfunction "A_1") (pintype "passive"))
      (node (ref "C14") (pin "2") (pinfunction "B_2") (pintype "passive"))
      (node (ref "C15") (pin "2") (pinfunction "B_2") (pintype "passive"))
      (node (ref "C16") (pin "2") (pinfunction "B_2") (pintype "passive"))
      (node (ref "C17") (pin "2") (pinfunction "B_2") (pintype "passive"))
      (node (ref "C18") (pin "2") (pinfunction "B_2") (pintype "passive"))
      (node (ref "C19") (pin "2") (pinfunction "B_2") (pintype "passive"))
      (node (ref "C2") (pin "2") (pinfunction "A_2") (pintype "passive"))
      (node (ref "C38") (pin "1") (pinfunction "1_1") (pintype "passive"))
      (node (ref "D1") (pin "1") (pinfunction "A_1") (pintype "passive"))
      (node (ref "J3") (pin "4") (pinfunction "VDD_4") (pintype "passive"))
      (node (ref "J5") (pin "P12") (pinfunction "P12_P12") (pintype "passive"))
      (node (ref "J5") (pin "P3") (pinfunction "P3_P3") (pintype "passive"))
      (node (ref "J5") (pin "P6") (pinfunction "P6_P6") (pintype "passive"))
      (node (ref "J5") (pin "P9") (pinfunction "P9_P9") (pintype "passive"))
      (node (ref "L1") (pin "2") (pinfunction "2_2") (pintype "passive"))
      (node (ref "P1") (pin "4") (pinfunction "4_4") (pintype "passive"))
      (node (ref "P1") (pin "7") (pinfunction "7_7") (pintype "passive"))
      (node (ref "R11") (pin "2") (pinfunction "2_2") (pintype "passive"))
      (node (ref "R12") (pin "2") (pinfunction "2_2") (pintype "passive"))
      (node (ref "R13") (pin "2") (pinfunction "2_2") (pintype "passive"))
      (node (ref "R16") (pin "2") (pinfunction "2_2") (pintype "passive"))
      (node (ref "R17") (pin "2") (pinfunction "2_2") (pintype "passive"))
      (node (ref "R18") (pin "2") (pinfunction "2_2") (pintype "passive"))
      (node (ref "R2") (pin "2") (pinfunction "2_2") (pintype "passive"))
      (node (ref "R25") (pin "1") (pinfunction "1_1") (pintype "passive"))
      (node (ref "R3") (pin "2") (pinfunction "2_2") (pintype "passive"))
      (node (ref "R4") (pin "2") (pinfunction "2_2") (pintype "passive"))
      (node (ref "R5") (pin "2") (pinfunction "2_2") (pintype "passive"))
      (node (ref "R6") (pin "2") (pinfunction "2_2") (pintype "passive"))
      (node (ref "U1") (pin "4") (pinfunction "FB_4") (pintype "passive"))
      (node (ref "U10") (pin "8") (pinfunction "VDD_8") (pintype "passive"))
      (node (ref "U2") (pin "20") (pinfunction "VDD_20") (pintype "passive"))
      (node (ref "U2") (pin "3") (pinfunction "VDDA_3") (pintype "passive"))
      (node (ref "U2") (pin "32") (pinfunction "VDD_32") (pintype "passive"))
      (node (ref "U2") (pin "36") (pinfunction "VCCPHY_36") (pintype "passive"))
      (node (ref "U2") (pin "44") (pinfunction "VDD_44") (pintype "passive"))
      (node (ref "U2") (pin "56") (pinfunction "VDD_56") (pintype "passive"))
      (node (ref "U2") (pin "68") (pinfunction "VDD_68") (pintype "passive"))
      (node (ref "U2") (pin "8") (pinfunction "VDD_8") (pintype "passive"))
      (node (ref "U2") (pin "81") (pinfunction "VDD_81") (pintype "passive"))
      (node (ref "U2") (pin "83") (pinfunction "VCCPHY_83") (pintype "passive"))
      (node (ref "U2") (pin "84") (pinfunction "VCCPHY_84") (pintype "passive"))
      (node (ref "U2") (pin "93") (pinfunction "VDD_93") (pintype "passive"))
      (node (ref "U2") (pin "98") (pinfunction "VDDA_98") (pintype "passive"))
      (node (ref "U4") (pin "2") (pinfunction "VS_2") (pintype "passive"))
    )
    (net (code "82") (name "VCC5V") (class "Default")
      (node (ref "C1") (pin "2") (pinfunction "A_2") (pintype "passive"))
      (node (ref "J2") (pin "1") (pinfunction "1_1") (pintype "passive"))
      (node (ref "J4") (pin "9") (pinfunction "9_9") (pintype "passive"))
      (node (ref "U1") (pin "1") (pinfunction "VIN_1") (pintype "power_in"))
      (node (ref "U3") (pin "10") (pinfunction "COM_10") (pintype "power_in"))
    )
    (net (code "83") (name "unconnected-(J2-Pad3)") (class "Default")
      (node (ref "J2") (pin "3") (pinfunction "3_3") (pintype "passive"))
    )
    (net (code "84") (name "unconnected-(J5-PadP4)") (class "Default")
      (node (ref "J5") (pin "P4") (pinfunction "P4_P4") (pintype "passive+no_connect"))
    )
    (net (code "85") (name "unconnected-(J5-PadP5)") (class "Default")
      (node (ref "J5") (pin "P5") (pinfunction "P5_P5") (pintype "passive+no_connect"))
    )
    (net (code "86") (name "unconnected-(U2-HIBn-Pad51)") (class "Default")
      (node (ref "U2") (pin "51") (pinfunction "HIBn_51") (pintype "passive+no_connect"))
    )
    (net (code "87") (name "unconnected-(U2-PE4-Pad6)") (class "Default")
      (node (ref "U2") (pin "6") (pinfunction "PE4_6") (pintype "passive"))
    )
    (net (code "88") (name "unconnected-(U2-PE5-Pad5)") (class "Default")
      (node (ref "U2") (pin "5") (pinfunction "PE5_5") (pintype "passive"))
    )
    (net (code "89") (name "unconnected-(U2-PE6{slash}C1o-Pad2)") (class "Default")
      (node (ref "U2") (pin "2") (pinfunction "PE6/C1o_2") (pintype "passive"))
    )
    (net (code "90") (name "unconnected-(U2-VBAT-Pad55)") (class "Default")
      (node (ref "U2") (pin "55") (pinfunction "VBAT_55") (pintype "passive+no_connect"))
    )
    (net (code "91") (name "unconnected-(U2-XOSC0-Pad52)") (class "Default")
      (node (ref "U2") (pin "52") (pinfunction "XOSC0_52") (pintype "passive+no_connect"))
    )
    (net (code "92") (name "unconnected-(U2-XOSC1-Pad53)") (class "Default")
      (node (ref "U2") (pin "53") (pinfunction "XOSC1_53") (pintype "passive+no_connect"))
    )
    (net (code "93") (name "unconnected-(U10-NC-Pad1)") (class "Default")
      (node (ref "U10") (pin "1") (pinfunction "NC_1") (pintype "passive+no_connect"))
    )
    (net (code "94") (name "unconnected-(U10-NC-Pad2)") (class "Default")
      (node (ref "U10") (pin "2") (pinfunction "NC_2") (pintype "passive+no_connect"))
    )
    (net (code "95") (name "unconnected-(U10-NC-Pad3)") (class "Default")
      (node (ref "U10") (pin "3") (pinfunction "NC_3") (pintype "passive+no_connect"))
    )
  )
)
